# FRA_bulkhead_v1.net
KiCad netlist of a schematic drawn in EAGLE
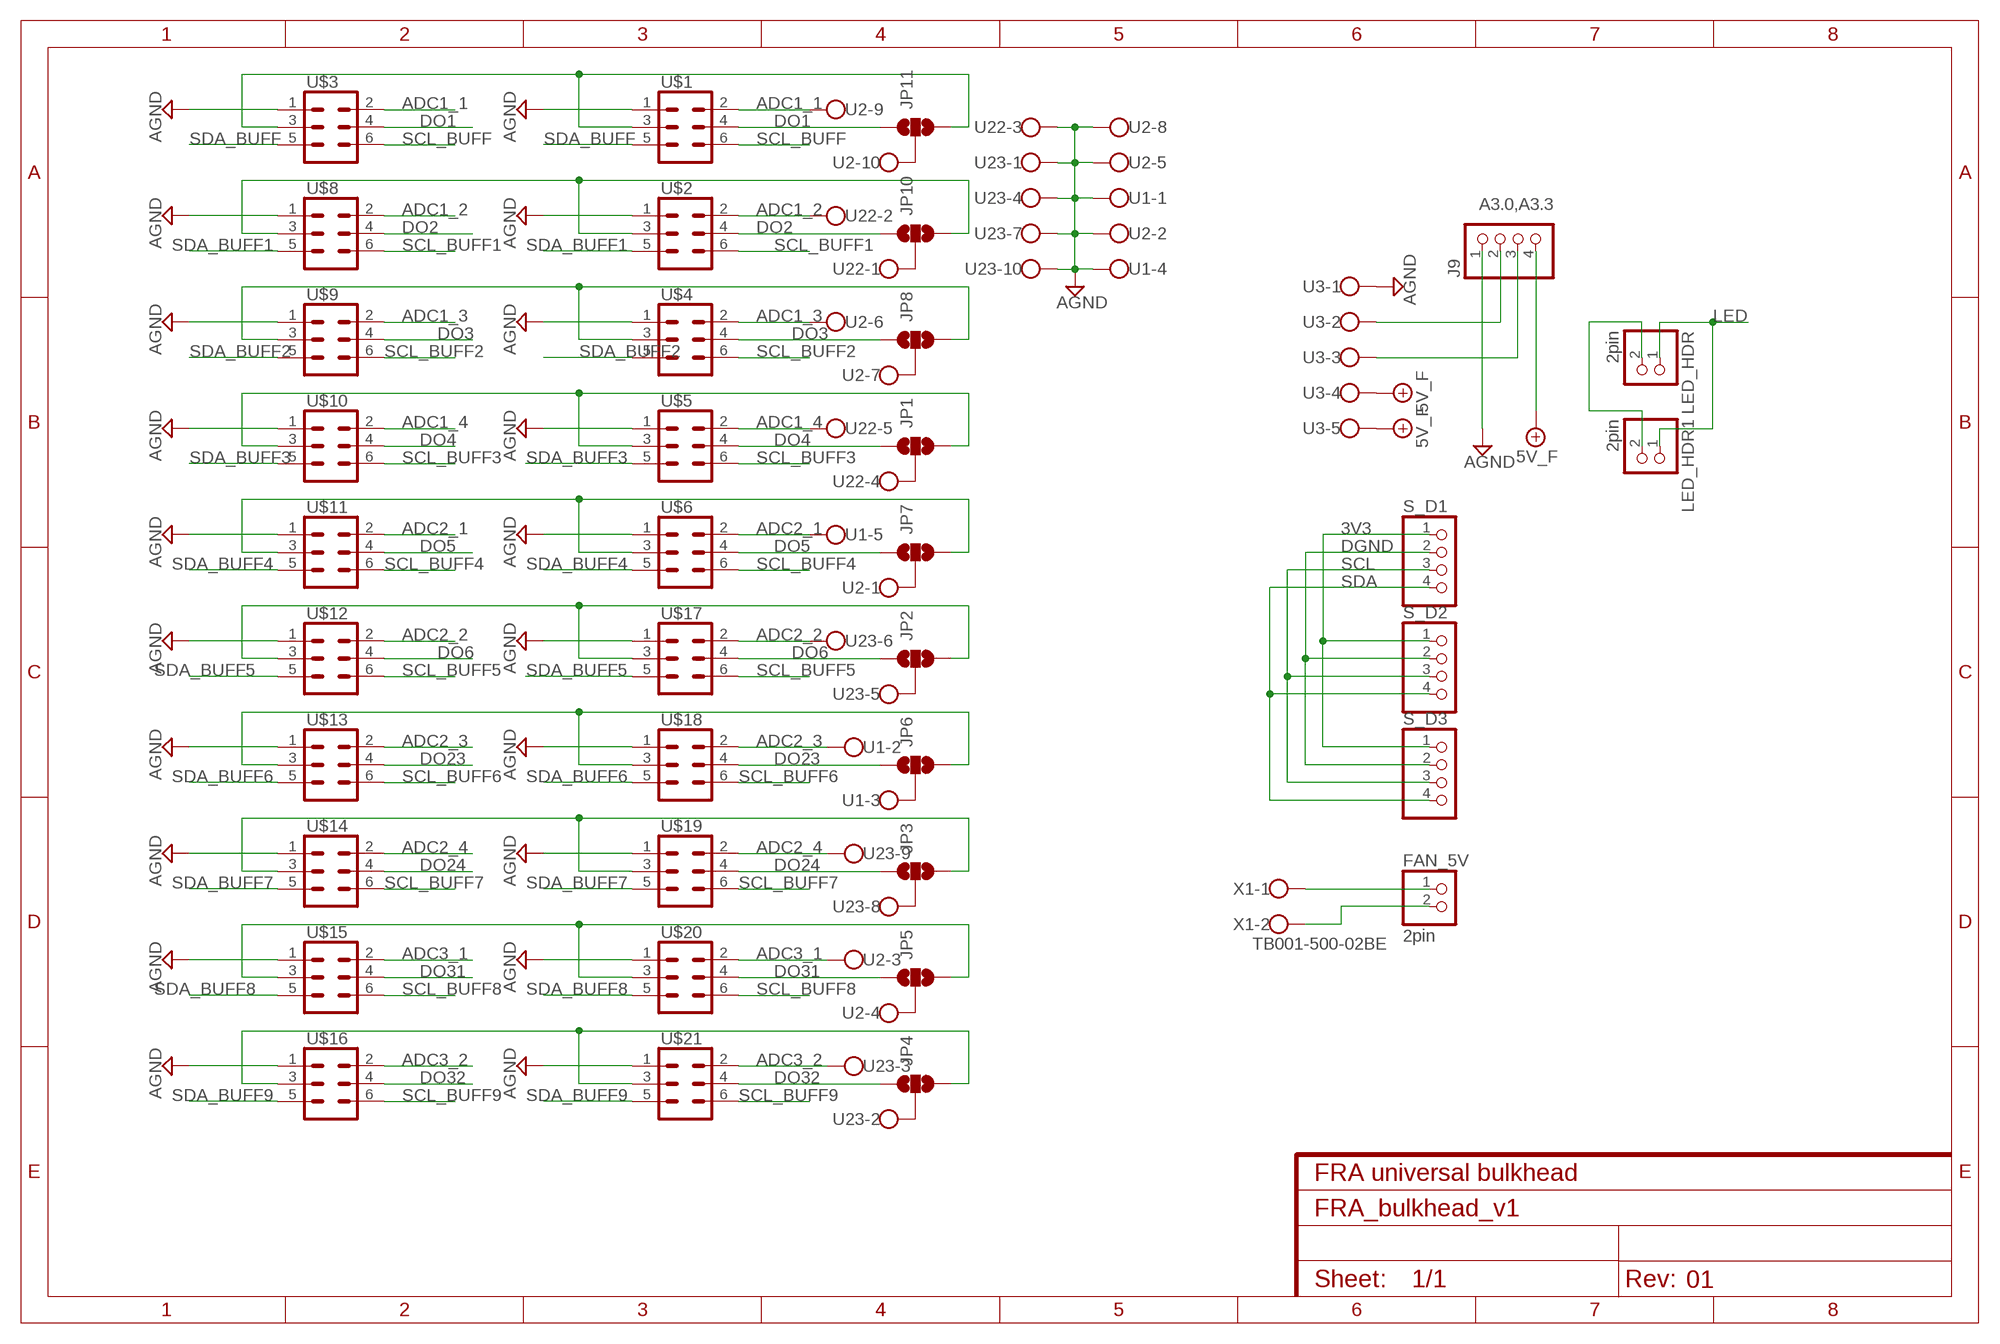
[diagram p0: schematic, sheet 1]

(export (version "E")
  (design (tool "Eeschema 10.0.6"))
  (components
    (comp (ref "FAN_5V")
      (value "2pin")
      (footprint "eagle-import:1X02")
      (fields (field (name "PARTNO") "TSW-102-07-G-S"))
      (libsource (lib "eagle-import") (part "PINHD-1X2"))
    )
    (comp (ref "J9")
      (value "4pin")
      (footprint "eagle-import:1X04")
      (fields (field (name "PARTNO") "61300411121"))
      (libsource (lib "eagle-import") (part "PINHD-1X4"))
    )
    (comp (ref "JP1")
      (value "JUMPER-SMT_3_NO_NO_SILK")
      (footprint "eagle-import:SMT-JUMPER_3_0-NO_TRACE_NO-SILK")
      (libsource (lib "eagle-import") (part "JUMPER-SMT_3_NO_NO_SILK"))
    )
    (comp (ref "JP2")
      (value "JUMPER-SMT_3_NO_NO_SILK")
      (footprint "eagle-import:SMT-JUMPER_3_0-NO_TRACE_NO-SILK")
      (libsource (lib "eagle-import") (part "JUMPER-SMT_3_NO_NO_SILK"))
    )
    (comp (ref "JP3")
      (value "JUMPER-SMT_3_NO_NO_SILK")
      (footprint "eagle-import:SMT-JUMPER_3_0-NO_TRACE_NO-SILK")
      (libsource (lib "eagle-import") (part "JUMPER-SMT_3_NO_NO_SILK"))
    )
    (comp (ref "JP4")
      (value "JUMPER-SMT_3_NO_NO_SILK")
      (footprint "eagle-import:SMT-JUMPER_3_0-NO_TRACE_NO-SILK")
      (libsource (lib "eagle-import") (part "JUMPER-SMT_3_NO_NO_SILK"))
    )
    (comp (ref "JP5")
      (value "JUMPER-SMT_3_NO_NO_SILK")
      (footprint "eagle-import:SMT-JUMPER_3_0-NO_TRACE_NO-SILK")
      (libsource (lib "eagle-import") (part "JUMPER-SMT_3_NO_NO_SILK"))
    )
    (comp (ref "JP6")
      (value "JUMPER-SMT_3_NO_NO_SILK")
      (footprint "eagle-import:SMT-JUMPER_3_0-NO_TRACE_NO-SILK")
      (libsource (lib "eagle-import") (part "JUMPER-SMT_3_NO_NO_SILK"))
    )
    (comp (ref "JP7")
      (value "JUMPER-SMT_3_NO_NO_SILK")
      (footprint "eagle-import:SMT-JUMPER_3_0-NO_TRACE_NO-SILK")
      (libsource (lib "eagle-import") (part "JUMPER-SMT_3_NO_NO_SILK"))
    )
    (comp (ref "JP8")
      (value "JUMPER-SMT_3_NO_NO_SILK")
      (footprint "eagle-import:SMT-JUMPER_3_0-NO_TRACE_NO-SILK")
      (libsource (lib "eagle-import") (part "JUMPER-SMT_3_NO_NO_SILK"))
    )
    (comp (ref "JP10")
      (value "JUMPER-SMT_3_NO_NO_SILK")
      (footprint "eagle-import:SMT-JUMPER_3_0-NO_TRACE_NO-SILK")
      (libsource (lib "eagle-import") (part "JUMPER-SMT_3_NO_NO_SILK"))
    )
    (comp (ref "JP11")
      (value "JUMPER-SMT_3_NO_NO_SILK")
      (footprint "eagle-import:SMT-JUMPER_3_0-NO_TRACE_NO-SILK")
      (libsource (lib "eagle-import") (part "JUMPER-SMT_3_NO_NO_SILK"))
    )
    (comp (ref "LED_HDR")
      (value "2pin")
      (footprint "eagle-import:1X02")
      (fields (field (name "PARTNO") "TSW-102-07-G-S"))
      (libsource (lib "eagle-import") (part "PINHD-1X2"))
    )
    (comp (ref "LED_HDR1")
      (value "2pin")
      (footprint "eagle-import:1X02")
      (fields (field (name "PARTNO") "TSW-102-07-G-S"))
      (libsource (lib "eagle-import") (part "PINHD-1X2"))
    )
    (comp (ref "S_D1")
      (value "4pin")
      (footprint "eagle-import:1X04")
      (fields (field (name "PARTNO") "61300411121"))
      (libsource (lib "eagle-import") (part "PINHD-1X4"))
    )
    (comp (ref "S_D2")
      (value "4pin")
      (footprint "eagle-import:1X04")
      (fields (field (name "PARTNO") "61300411121"))
      (libsource (lib "eagle-import") (part "PINHD-1X4"))
    )
    (comp (ref "S_D3")
      (value "4pin")
      (footprint "eagle-import:1X04")
      (fields (field (name "PARTNO") "61300411121"))
      (libsource (lib "eagle-import") (part "PINHD-1X4"))
    )
    (comp (ref "U$1")
      (value "CONN_03X2_WE_61200621621")
      (footprint "eagle-import:WE_61200621621")
      (fields (field (name "PARTNO") "61200621621"))
      (libsource (lib "eagle-import") (part "CONN_03X2_WE_61200621621"))
    )
    (comp (ref "U$2")
      (value "CONN_03X2_WE_61200621621")
      (footprint "eagle-import:WE_61200621621")
      (fields (field (name "PARTNO") "61200621621"))
      (libsource (lib "eagle-import") (part "CONN_03X2_WE_61200621621"))
    )
    (comp (ref "U$3")
      (value "CONN_03X2_WE_61200621621")
      (footprint "eagle-import:WE_61200621621")
      (fields (field (name "PARTNO") "61200621621"))
      (libsource (lib "eagle-import") (part "CONN_03X2_WE_61200621621"))
    )
    (comp (ref "U$4")
      (value "CONN_03X2_WE_61200621621")
      (footprint "eagle-import:WE_61200621621")
      (fields (field (name "PARTNO") "61200621621"))
      (libsource (lib "eagle-import") (part "CONN_03X2_WE_61200621621"))
    )
    (comp (ref "U$5")
      (value "CONN_03X2_WE_61200621621")
      (footprint "eagle-import:WE_61200621621")
      (fields (field (name "PARTNO") "61200621621"))
      (libsource (lib "eagle-import") (part "CONN_03X2_WE_61200621621"))
    )
    (comp (ref "U$6")
      (value "CONN_03X2_WE_61200621621")
      (footprint "eagle-import:WE_61200621621")
      (fields (field (name "PARTNO") "61200621621"))
      (libsource (lib "eagle-import") (part "CONN_03X2_WE_61200621621"))
    )
    (comp (ref "U$8")
      (value "CONN_03X2_WE_61200621621")
      (footprint "eagle-import:WE_61200621621")
      (fields (field (name "PARTNO") "61200621621"))
      (libsource (lib "eagle-import") (part "CONN_03X2_WE_61200621621"))
    )
    (comp (ref "U$9")
      (value "CONN_03X2_WE_61200621621")
      (footprint "eagle-import:WE_61200621621")
      (fields (field (name "PARTNO") "61200621621"))
      (libsource (lib "eagle-import") (part "CONN_03X2_WE_61200621621"))
    )
    (comp (ref "U$10")
      (value "CONN_03X2_WE_61200621621")
      (footprint "eagle-import:WE_61200621621")
      (fields (field (name "PARTNO") "61200621621"))
      (libsource (lib "eagle-import") (part "CONN_03X2_WE_61200621621"))
    )
    (comp (ref "U$11")
      (value "CONN_03X2_WE_61200621621")
      (footprint "eagle-import:WE_61200621621")
      (fields (field (name "PARTNO") "61200621621"))
      (libsource (lib "eagle-import") (part "CONN_03X2_WE_61200621621"))
    )
    (comp (ref "U$12")
      (value "CONN_03X2_WE_61200621621")
      (footprint "eagle-import:WE_61200621621")
      (fields (field (name "PARTNO") "61200621621"))
      (libsource (lib "eagle-import") (part "CONN_03X2_WE_61200621621"))
    )
    (comp (ref "U$13")
      (value "CONN_03X2_WE_61200621621")
      (footprint "eagle-import:WE_61200621621")
      (fields (field (name "PARTNO") "61200621621"))
      (libsource (lib "eagle-import") (part "CONN_03X2_WE_61200621621"))
    )
    (comp (ref "U$14")
      (value "CONN_03X2_WE_61200621621")
      (footprint "eagle-import:WE_61200621621")
      (fields (field (name "PARTNO") "61200621621"))
      (libsource (lib "eagle-import") (part "CONN_03X2_WE_61200621621"))
    )
    (comp (ref "U$15")
      (value "CONN_03X2_WE_61200621621")
      (footprint "eagle-import:WE_61200621621")
      (fields (field (name "PARTNO") "61200621621"))
      (libsource (lib "eagle-import") (part "CONN_03X2_WE_61200621621"))
    )
    (comp (ref "U$16")
      (value "CONN_03X2_WE_61200621621")
      (footprint "eagle-import:WE_61200621621")
      (fields (field (name "PARTNO") "61200621621"))
      (libsource (lib "eagle-import") (part "CONN_03X2_WE_61200621621"))
    )
    (comp (ref "U$17")
      (value "CONN_03X2_WE_61200621621")
      (footprint "eagle-import:WE_61200621621")
      (fields (field (name "PARTNO") "61200621621"))
      (libsource (lib "eagle-import") (part "CONN_03X2_WE_61200621621"))
    )
    (comp (ref "U$18")
      (value "CONN_03X2_WE_61200621621")
      (footprint "eagle-import:WE_61200621621")
      (fields (field (name "PARTNO") "61200621621"))
      (libsource (lib "eagle-import") (part "CONN_03X2_WE_61200621621"))
    )
    (comp (ref "U$19")
      (value "CONN_03X2_WE_61200621621")
      (footprint "eagle-import:WE_61200621621")
      (fields (field (name "PARTNO") "61200621621"))
      (libsource (lib "eagle-import") (part "CONN_03X2_WE_61200621621"))
    )
    (comp (ref "U$20")
      (value "CONN_03X2_WE_61200621621")
      (footprint "eagle-import:WE_61200621621")
      (fields (field (name "PARTNO") "61200621621"))
      (libsource (lib "eagle-import") (part "CONN_03X2_WE_61200621621"))
    )
    (comp (ref "U$21")
      (value "CONN_03X2_WE_61200621621")
      (footprint "eagle-import:WE_61200621621")
      (fields (field (name "PARTNO") "61200621621"))
      (libsource (lib "eagle-import") (part "CONN_03X2_WE_61200621621"))
    )
    (comp (ref "U1")
      (value "TB003V-500-P05BERIGHTANGLE-NORMAL")
      (footprint "eagle-import:TB003-500-P05BE")
      (libsource (lib "eagle-import") (part "TB003V-500-P05BERIGHTANGLE-NORMAL"))
    )
    (comp (ref "U2")
      (value "TB003V-500-P10BERIGHTANGLE-NORMAL")
      (footprint "eagle-import:TB003-500-P10BE")
      (libsource (lib "eagle-import") (part "TB003V-500-P10BERIGHTANGLE-NORMAL"))
    )
    (comp (ref "U3")
      (value "TB003V-500-P05BERIGHTANGLE-NORMAL")
      (footprint "eagle-import:TB003-500-P05BE")
      (libsource (lib "eagle-import") (part "TB003V-500-P05BERIGHTANGLE-NORMAL"))
    )
    (comp (ref "U22")
      (value "TB003V-500-P05BERIGHTANGLE-NORMAL")
      (footprint "eagle-import:TB003-500-P05BE")
      (libsource (lib "eagle-import") (part "TB003V-500-P05BERIGHTANGLE-NORMAL"))
    )
    (comp (ref "U23")
      (value "TB003V-500-P10BERIGHTANGLE-NORMAL")
      (footprint "eagle-import:TB003-500-P10BE")
      (libsource (lib "eagle-import") (part "TB003V-500-P10BERIGHTANGLE-NORMAL"))
    )
    (comp (ref "X1")
      (value "TB001-500-02BE")
      (footprint "eagle-import:W237-102")
      (fields (field (name "MPN") "237-102") (field (name "PARTNO") "TB001-500-02BE"))
      (libsource (lib "eagle-import") (part "W237-102"))
    )
  )
  (nets
    (net (code "1") (name "/3V3") (class "Default")
      (node (ref "S_D1") (pin "1") (pinfunction "1_1") (pintype "passive"))
      (node (ref "S_D2") (pin "1") (pinfunction "1_1") (pintype "passive"))
      (node (ref "S_D3") (pin "1") (pinfunction "1_1") (pintype "passive"))
    )
    (net (code "2") (name "/ADC1_1") (class "Default")
      (node (ref "U$1") (pin "2") (pinfunction "2_2") (pintype "bidirectional"))
      (node (ref "U$3") (pin "2") (pinfunction "2_2") (pintype "bidirectional"))
      (node (ref "U2") (pin "9") (pinfunction "KL_9") (pintype "passive"))
    )
    (net (code "3") (name "/ADC1_2") (class "Default")
      (node (ref "U$2") (pin "2") (pinfunction "2_2") (pintype "bidirectional"))
      (node (ref "U$8") (pin "2") (pinfunction "2_2") (pintype "bidirectional"))
      (node (ref "U22") (pin "2") (pinfunction "KL_2") (pintype "passive"))
    )
    (net (code "4") (name "/ADC1_3") (class "Default")
      (node (ref "U$4") (pin "2") (pinfunction "2_2") (pintype "bidirectional"))
      (node (ref "U$9") (pin "2") (pinfunction "2_2") (pintype "bidirectional"))
      (node (ref "U2") (pin "6") (pinfunction "KL_6") (pintype "passive"))
    )
    (net (code "5") (name "/ADC1_4") (class "Default")
      (node (ref "U$10") (pin "2") (pinfunction "2_2") (pintype "bidirectional"))
      (node (ref "U$5") (pin "2") (pinfunction "2_2") (pintype "bidirectional"))
      (node (ref "U22") (pin "5") (pinfunction "KL_5") (pintype "passive"))
    )
    (net (code "6") (name "/ADC2_1") (class "Default")
      (node (ref "U$11") (pin "2") (pinfunction "2_2") (pintype "bidirectional"))
      (node (ref "U$6") (pin "2") (pinfunction "2_2") (pintype "bidirectional"))
      (node (ref "U1") (pin "5") (pinfunction "KL_5") (pintype "passive"))
    )
    (net (code "7") (name "/ADC2_2") (class "Default")
      (node (ref "U$12") (pin "2") (pinfunction "2_2") (pintype "bidirectional"))
      (node (ref "U$17") (pin "2") (pinfunction "2_2") (pintype "bidirectional"))
      (node (ref "U23") (pin "6") (pinfunction "KL_6") (pintype "passive"))
    )
    (net (code "8") (name "/ADC2_3") (class "Default")
      (node (ref "U$13") (pin "2") (pinfunction "2_2") (pintype "bidirectional"))
      (node (ref "U$18") (pin "2") (pinfunction "2_2") (pintype "bidirectional"))
      (node (ref "U1") (pin "2") (pinfunction "KL_2") (pintype "passive"))
    )
    (net (code "9") (name "/ADC2_4") (class "Default")
      (node (ref "U$14") (pin "2") (pinfunction "2_2") (pintype "bidirectional"))
      (node (ref "U$19") (pin "2") (pinfunction "2_2") (pintype "bidirectional"))
      (node (ref "U23") (pin "9") (pinfunction "KL_9") (pintype "passive"))
    )
    (net (code "10") (name "/ADC3_1") (class "Default")
      (node (ref "U$15") (pin "2") (pinfunction "2_2") (pintype "bidirectional"))
      (node (ref "U$20") (pin "2") (pinfunction "2_2") (pintype "bidirectional"))
      (node (ref "U2") (pin "3") (pinfunction "KL_3") (pintype "passive"))
    )
    (net (code "11") (name "/ADC3_2") (class "Default")
      (node (ref "U$16") (pin "2") (pinfunction "2_2") (pintype "bidirectional"))
      (node (ref "U$21") (pin "2") (pinfunction "2_2") (pintype "bidirectional"))
      (node (ref "U23") (pin "3") (pinfunction "KL_3") (pintype "passive"))
    )
    (net (code "12") (name "/DGND") (class "Default")
      (node (ref "S_D1") (pin "2") (pinfunction "2_2") (pintype "passive"))
      (node (ref "S_D2") (pin "2") (pinfunction "2_2") (pintype "passive"))
      (node (ref "S_D3") (pin "2") (pinfunction "2_2") (pintype "passive"))
    )
    (net (code "13") (name "/DO1") (class "Default")
      (node (ref "JP11") (pin "1") (pinfunction "1_1") (pintype "passive"))
      (node (ref "U$1") (pin "4") (pinfunction "4_4") (pintype "bidirectional"))
      (node (ref "U$3") (pin "4") (pinfunction "4_4") (pintype "bidirectional"))
    )
    (net (code "14") (name "/DO2") (class "Default")
      (node (ref "JP10") (pin "1") (pinfunction "1_1") (pintype "passive"))
      (node (ref "U$2") (pin "4") (pinfunction "4_4") (pintype "bidirectional"))
      (node (ref "U$8") (pin "4") (pinfunction "4_4") (pintype "bidirectional"))
    )
    (net (code "15") (name "/DO3") (class "Default")
      (node (ref "JP8") (pin "1") (pinfunction "1_1") (pintype "passive"))
      (node (ref "U$4") (pin "4") (pinfunction "4_4") (pintype "bidirectional"))
      (node (ref "U$9") (pin "4") (pinfunction "4_4") (pintype "bidirectional"))
    )
    (net (code "16") (name "/DO4") (class "Default")
      (node (ref "JP1") (pin "1") (pinfunction "1_1") (pintype "passive"))
      (node (ref "U$10") (pin "4") (pinfunction "4_4") (pintype "bidirectional"))
      (node (ref "U$5") (pin "4") (pinfunction "4_4") (pintype "bidirectional"))
    )
    (net (code "17") (name "/DO5") (class "Default")
      (node (ref "JP7") (pin "1") (pinfunction "1_1") (pintype "passive"))
      (node (ref "U$11") (pin "4") (pinfunction "4_4") (pintype "bidirectional"))
      (node (ref "U$6") (pin "4") (pinfunction "4_4") (pintype "bidirectional"))
    )
    (net (code "18") (name "/DO6") (class "Default")
      (node (ref "JP2") (pin "1") (pinfunction "1_1") (pintype "passive"))
      (node (ref "U$12") (pin "4") (pinfunction "4_4") (pintype "bidirectional"))
      (node (ref "U$17") (pin "4") (pinfunction "4_4") (pintype "bidirectional"))
    )
    (net (code "19") (name "/DO23") (class "Default")
      (node (ref "JP6") (pin "1") (pinfunction "1_1") (pintype "passive"))
      (node (ref "U$13") (pin "4") (pinfunction "4_4") (pintype "bidirectional"))
      (node (ref "U$18") (pin "4") (pinfunction "4_4") (pintype "bidirectional"))
    )
    (net (code "20") (name "/DO24") (class "Default")
      (node (ref "JP3") (pin "1") (pinfunction "1_1") (pintype "passive"))
      (node (ref "U$14") (pin "4") (pinfunction "4_4") (pintype "bidirectional"))
      (node (ref "U$19") (pin "4") (pinfunction "4_4") (pintype "bidirectional"))
    )
    (net (code "21") (name "/DO31") (class "Default")
      (node (ref "JP5") (pin "1") (pinfunction "1_1") (pintype "passive"))
      (node (ref "U$15") (pin "4") (pinfunction "4_4") (pintype "bidirectional"))
      (node (ref "U$20") (pin "4") (pinfunction "4_4") (pintype "bidirectional"))
    )
    (net (code "22") (name "/DO32") (class "Default")
      (node (ref "JP4") (pin "1") (pinfunction "1_1") (pintype "passive"))
      (node (ref "U$16") (pin "4") (pinfunction "4_4") (pintype "bidirectional"))
      (node (ref "U$21") (pin "4") (pinfunction "4_4") (pintype "bidirectional"))
    )
    (net (code "23") (name "/LED") (class "Default")
      (node (ref "LED_HDR") (pin "1") (pinfunction "1_1") (pintype "passive"))
      (node (ref "LED_HDR1") (pin "1") (pinfunction "1_1") (pintype "passive"))
    )
    (net (code "24") (name "/SCL") (class "Default")
      (node (ref "S_D1") (pin "3") (pinfunction "3_3") (pintype "passive"))
      (node (ref "S_D2") (pin "3") (pinfunction "3_3") (pintype "passive"))
      (node (ref "S_D3") (pin "3") (pinfunction "3_3") (pintype "passive"))
    )
    (net (code "25") (name "/SCL_BUFF") (class "Default")
      (node (ref "U$1") (pin "6") (pinfunction "6_6") (pintype "bidirectional"))
      (node (ref "U$3") (pin "6") (pinfunction "6_6") (pintype "bidirectional"))
    )
    (net (code "26") (name "/SCL_BUFF1") (class "Default")
      (node (ref "U$2") (pin "6") (pinfunction "6_6") (pintype "bidirectional"))
      (node (ref "U$8") (pin "6") (pinfunction "6_6") (pintype "bidirectional"))
    )
    (net (code "27") (name "/SCL_BUFF2") (class "Default")
      (node (ref "U$4") (pin "6") (pinfunction "6_6") (pintype "bidirectional"))
      (node (ref "U$9") (pin "6") (pinfunction "6_6") (pintype "bidirectional"))
    )
    (net (code "28") (name "/SCL_BUFF3") (class "Default")
      (node (ref "U$10") (pin "6") (pinfunction "6_6") (pintype "bidirectional"))
      (node (ref "U$5") (pin "6") (pinfunction "6_6") (pintype "bidirectional"))
    )
    (net (code "29") (name "/SCL_BUFF4") (class "Default")
      (node (ref "U$11") (pin "6") (pinfunction "6_6") (pintype "bidirectional"))
      (node (ref "U$6") (pin "6") (pinfunction "6_6") (pintype "bidirectional"))
    )
    (net (code "30") (name "/SCL_BUFF5") (class "Default")
      (node (ref "U$12") (pin "6") (pinfunction "6_6") (pintype "bidirectional"))
      (node (ref "U$17") (pin "6") (pinfunction "6_6") (pintype "bidirectional"))
    )
    (net (code "31") (name "/SCL_BUFF6") (class "Default")
      (node (ref "U$13") (pin "6") (pinfunction "6_6") (pintype "bidirectional"))
      (node (ref "U$18") (pin "6") (pinfunction "6_6") (pintype "bidirectional"))
    )
    (net (code "32") (name "/SCL_BUFF7") (class "Default")
      (node (ref "U$14") (pin "6") (pinfunction "6_6") (pintype "bidirectional"))
      (node (ref "U$19") (pin "6") (pinfunction "6_6") (pintype "bidirectional"))
    )
    (net (code "33") (name "/SCL_BUFF8") (class "Default")
      (node (ref "U$15") (pin "6") (pinfunction "6_6") (pintype "bidirectional"))
      (node (ref "U$20") (pin "6") (pinfunction "6_6") (pintype "bidirectional"))
    )
    (net (code "34") (name "/SCL_BUFF9") (class "Default")
      (node (ref "U$16") (pin "6") (pinfunction "6_6") (pintype "bidirectional"))
      (node (ref "U$21") (pin "6") (pinfunction "6_6") (pintype "bidirectional"))
    )
    (net (code "35") (name "/SDA") (class "Default")
      (node (ref "S_D1") (pin "4") (pinfunction "4_4") (pintype "passive"))
      (node (ref "S_D2") (pin "4") (pinfunction "4_4") (pintype "passive"))
      (node (ref "S_D3") (pin "4") (pinfunction "4_4") (pintype "passive"))
    )
    (net (code "36") (name "/SDA_BUFF") (class "Default")
      (node (ref "U$1") (pin "5") (pinfunction "5_5") (pintype "bidirectional"))
      (node (ref "U$3") (pin "5") (pinfunction "5_5") (pintype "bidirectional"))
    )
    (net (code "37") (name "/SDA_BUFF1") (class "Default")
      (node (ref "U$2") (pin "5") (pinfunction "5_5") (pintype "bidirectional"))
      (node (ref "U$8") (pin "5") (pinfunction "5_5") (pintype "bidirectional"))
    )
    (net (code "38") (name "/SDA_BUFF2") (class "Default")
      (node (ref "U$4") (pin "5") (pinfunction "5_5") (pintype "bidirectional"))
      (node (ref "U$9") (pin "5") (pinfunction "5_5") (pintype "bidirectional"))
    )
    (net (code "39") (name "/SDA_BUFF3") (class "Default")
      (node (ref "U$10") (pin "5") (pinfunction "5_5") (pintype "bidirectional"))
      (node (ref "U$5") (pin "5") (pinfunction "5_5") (pintype "bidirectional"))
    )
    (net (code "40") (name "/SDA_BUFF4") (class "Default")
      (node (ref "U$11") (pin "5") (pinfunction "5_5") (pintype "bidirectional"))
      (node (ref "U$6") (pin "5") (pinfunction "5_5") (pintype "bidirectional"))
    )
    (net (code "41") (name "/SDA_BUFF5") (class "Default")
      (node (ref "U$12") (pin "5") (pinfunction "5_5") (pintype "bidirectional"))
      (node (ref "U$17") (pin "5") (pinfunction "5_5") (pintype "bidirectional"))
    )
    (net (code "42") (name "/SDA_BUFF6") (class "Default")
      (node (ref "U$13") (pin "5") (pinfunction "5_5") (pintype "bidirectional"))
      (node (ref "U$18") (pin "5") (pinfunction "5_5") (pintype "bidirectional"))
    )
    (net (code "43") (name "/SDA_BUFF7") (class "Default")
      (node (ref "U$14") (pin "5") (pinfunction "5_5") (pintype "bidirectional"))
      (node (ref "U$19") (pin "5") (pinfunction "5_5") (pintype "bidirectional"))
    )
    (net (code "44") (name "/SDA_BUFF8") (class "Default")
      (node (ref "U$15") (pin "5") (pinfunction "5_5") (pintype "bidirectional"))
      (node (ref "U$20") (pin "5") (pinfunction "5_5") (pintype "bidirectional"))
    )
    (net (code "45") (name "/SDA_BUFF9") (class "Default")
      (node (ref "U$16") (pin "5") (pinfunction "5_5") (pintype "bidirectional"))
      (node (ref "U$21") (pin "5") (pinfunction "5_5") (pintype "bidirectional"))
    )
    (net (code "46") (name "5V_F") (class "Default")
      (node (ref "J9") (pin "4") (pinfunction "4_4") (pintype "passive"))
      (node (ref "U3") (pin "4") (pinfunction "KL_4") (pintype "passive"))
      (node (ref "U3") (pin "5") (pinfunction "KL_5") (pintype "passive"))
    )
    (net (code "47") (name "AGND") (class "Default")
      (node (ref "J9") (pin "1") (pinfunction "1_1") (pintype "passive"))
      (node (ref "U$1") (pin "1") (pinfunction "1_1") (pintype "bidirectional"))
      (node (ref "U$10") (pin "1") (pinfunction "1_1") (pintype "bidirectional"))
      (node (ref "U$11") (pin "1") (pinfunction "1_1") (pintype "bidirectional"))
      (node (ref "U$12") (pin "1") (pinfunction "1_1") (pintype "bidirectional"))
      (node (ref "U$13") (pin "1") (pinfunction "1_1") (pintype "bidirectional"))
      (node (ref "U$14") (pin "1") (pinfunction "1_1") (pintype "bidirectional"))
      (node (ref "U$15") (pin "1") (pinfunction "1_1") (pintype "bidirectional"))
      (node (ref "U$16") (pin "1") (pinfunction "1_1") (pintype "bidirectional"))
      (node (ref "U$17") (pin "1") (pinfunction "1_1") (pintype "bidirectional"))
      (node (ref "U$18") (pin "1") (pinfunction "1_1") (pintype "bidirectional"))
      (node (ref "U$19") (pin "1") (pinfunction "1_1") (pintype "bidirectional"))
      (node (ref "U$2") (pin "1") (pinfunction "1_1") (pintype "bidirectional"))
      (node (ref "U$20") (pin "1") (pinfunction "1_1") (pintype "bidirectional"))
      (node (ref "U$21") (pin "1") (pinfunction "1_1") (pintype "bidirectional"))
      (node (ref "U$3") (pin "1") (pinfunction "1_1") (pintype "bidirectional"))
      (node (ref "U$4") (pin "1") (pinfunction "1_1") (pintype "bidirectional"))
      (node (ref "U$5") (pin "1") (pinfunction "1_1") (pintype "bidirectional"))
      (node (ref "U$6") (pin "1") (pinfunction "1_1") (pintype "bidirectional"))
      (node (ref "U$8") (pin "1") (pinfunction "1_1") (pintype "bidirectional"))
      (node (ref "U$9") (pin "1") (pinfunction "1_1") (pintype "bidirectional"))
      (node (ref "U1") (pin "1") (pinfunction "KL_1") (pintype "passive"))
      (node (ref "U1") (pin "4") (pinfunction "KL_4") (pintype "passive"))
      (node (ref "U2") (pin "2") (pinfunction "KL_2") (pintype "passive"))
      (node (ref "U2") (pin "5") (pinfunction "KL_5") (pintype "passive"))
      (node (ref "U2") (pin "8") (pinfunction "KL_8") (pintype "passive"))
      (node (ref "U22") (pin "3") (pinfunction "KL_3") (pintype "passive"))
      (node (ref "U23") (pin "1") (pinfunction "KL_1") (pintype "passive"))
      (node (ref "U23") (pin "10") (pinfunction "KL_10") (pintype "passive"))
      (node (ref "U23") (pin "4") (pinfunction "KL_4") (pintype "passive"))
      (node (ref "U23") (pin "7") (pinfunction "KL_7") (pintype "passive"))
      (node (ref "U3") (pin "1") (pinfunction "KL_1") (pintype "passive"))
    )
    (net (code "48") (name "Net-(JP1-Pad3)") (class "Default")
      (node (ref "JP1") (pin "3") (pinfunction "3_3") (pintype "passive"))
      (node (ref "U$10") (pin "3") (pinfunction "3_3") (pintype "bidirectional"))
      (node (ref "U$5") (pin "3") (pinfunction "3_3") (pintype "bidirectional"))
    )
    (net (code "49") (name "Net-(JP2-Pad3)") (class "Default")
      (node (ref "JP2") (pin "3") (pinfunction "3_3") (pintype "passive"))
      (node (ref "U$12") (pin "3") (pinfunction "3_3") (pintype "bidirectional"))
      (node (ref "U$17") (pin "3") (pinfunction "3_3") (pintype "bidirectional"))
    )
    (net (code "50") (name "Net-(JP3-Pad3)") (class "Default")
      (node (ref "JP3") (pin "3") (pinfunction "3_3") (pintype "passive"))
      (node (ref "U$14") (pin "3") (pinfunction "3_3") (pintype "bidirectional"))
      (node (ref "U$19") (pin "3") (pinfunction "3_3") (pintype "bidirectional"))
    )
    (net (code "51") (name "Net-(JP4-Pad3)") (class "Default")
      (node (ref "JP4") (pin "3") (pinfunction "3_3") (pintype "passive"))
      (node (ref "U$16") (pin "3") (pinfunction "3_3") (pintype "bidirectional"))
      (node (ref "U$21") (pin "3") (pinfunction "3_3") (pintype "bidirectional"))
    )
    (net (code "52") (name "Net-(JP5-Pad3)") (class "Default")
      (node (ref "JP5") (pin "3") (pinfunction "3_3") (pintype "passive"))
      (node (ref "U$15") (pin "3") (pinfunction "3_3") (pintype "bidirectional"))
      (node (ref "U$20") (pin "3") (pinfunction "3_3") (pintype "bidirectional"))
    )
    (net (code "53") (name "Net-(JP6-Pad3)") (class "Default")
      (node (ref "JP6") (pin "3") (pinfunction "3_3") (pintype "passive"))
      (node (ref "U$13") (pin "3") (pinfunction "3_3") (pintype "bidirectional"))
      (node (ref "U$18") (pin "3") (pinfunction "3_3") (pintype "bidirectional"))
    )
    (net (code "54") (name "Net-(JP7-Pad3)") (class "Default")
      (node (ref "JP7") (pin "3") (pinfunction "3_3") (pintype "passive"))
      (node (ref "U$11") (pin "3") (pinfunction "3_3") (pintype "bidirectional"))
      (node (ref "U$6") (pin "3") (pinfunction "3_3") (pintype "bidirectional"))
    )
    (net (code "55") (name "Net-(JP8-Pad3)") (class "Default")
      (node (ref "JP8") (pin "3") (pinfunction "3_3") (pintype "passive"))
      (node (ref "U$4") (pin "3") (pinfunction "3_3") (pintype "bidirectional"))
      (node (ref "U$9") (pin "3") (pinfunction "3_3") (pintype "bidirectional"))
    )
    (net (code "56") (name "Net-(JP10-Pad3)") (class "Default")
      (node (ref "JP10") (pin "3") (pinfunction "3_3") (pintype "passive"))
      (node (ref "U$2") (pin "3") (pinfunction "3_3") (pintype "bidirectional"))
      (node (ref "U$8") (pin "3") (pinfunction "3_3") (pintype "bidirectional"))
    )
    (net (code "57") (name "Net-(JP11-Pad3)") (class "Default")
      (node (ref "JP11") (pin "3") (pinfunction "3_3") (pintype "passive"))
      (node (ref "U$1") (pin "3") (pinfunction "3_3") (pintype "bidirectional"))
      (node (ref "U$3") (pin "3") (pinfunction "3_3") (pintype "bidirectional"))
    )
    (net (code "58") (name "Net-(LED_HDR-Pad2)") (class "Default")
      (node (ref "LED_HDR") (pin "2") (pinfunction "2_2") (pintype "passive"))
      (node (ref "LED_HDR1") (pin "2") (pinfunction "2_2") (pintype "passive"))
    )
    (net (code "59") (name "Net-(U1C-KL)") (class "Default")
      (node (ref "JP6") (pin "2") (pinfunction "2_2") (pintype "passive"))
      (node (ref "U1") (pin "3") (pinfunction "KL_3") (pintype "passive"))
    )
    (net (code "60") (name "Net-(U2A-KL)") (class "Default")
      (node (ref "JP7") (pin "2") (pinfunction "2_2") (pintype "passive"))
      (node (ref "U2") (pin "1") (pinfunction "KL_1") (pintype "passive"))
    )
    (net (code "61") (name "Net-(U2B-KL)") (class "Default")
      (node (ref "JP11") (pin "2") (pinfunction "2_2") (pintype "passive"))
      (node (ref "U2") (pin "10") (pinfunction "KL_10") (pintype "passive"))
    )
    (net (code "62") (name "Net-(U2E-KL)") (class "Default")
      (node (ref "JP5") (pin "2") (pinfunction "2_2") (pintype "passive"))
      (node (ref "U2") (pin "4") (pinfunction "KL_4") (pintype "passive"))
    )
    (net (code "63") (name "Net-(U2H-KL)") (class "Default")
      (node (ref "JP8") (pin "2") (pinfunction "2_2") (pintype "passive"))
      (node (ref "U2") (pin "7") (pinfunction "KL_7") (pintype "passive"))
    )
    (net (code "64") (name "Net-(U3B-KL)") (class "Default")
      (node (ref "J9") (pin "2") (pinfunction "2_2") (pintype "passive"))
      (node (ref "U3") (pin "2") (pinfunction "KL_2") (pintype "passive"))
    )
    (net (code "65") (name "Net-(U3C-KL)") (class "Default")
      (node (ref "J9") (pin "3") (pinfunction "3_3") (pintype "passive"))
      (node (ref "U3") (pin "3") (pinfunction "KL_3") (pintype "passive"))
    )
    (net (code "66") (name "Net-(U22A-KL)") (class "Default")
      (node (ref "JP10") (pin "2") (pinfunction "2_2") (pintype "passive"))
      (node (ref "U22") (pin "1") (pinfunction "KL_1") (pintype "passive"))
    )
    (net (code "67") (name "Net-(U22D-KL)") (class "Default")
      (node (ref "JP1") (pin "2") (pinfunction "2_2") (pintype "passive"))
      (node (ref "U22") (pin "4") (pinfunction "KL_4") (pintype "passive"))
    )
    (net (code "68") (name "Net-(U23C-KL)") (class "Default")
      (node (ref "JP4") (pin "2") (pinfunction "2_2") (pintype "passive"))
      (node (ref "U23") (pin "2") (pinfunction "KL_2") (pintype "passive"))
    )
    (net (code "69") (name "Net-(U23F-KL)") (class "Default")
      (node (ref "JP2") (pin "2") (pinfunction "2_2") (pintype "passive"))
      (node (ref "U23") (pin "5") (pinfunction "KL_5") (pintype "passive"))
    )
    (net (code "70") (name "Net-(U23I-KL)") (class "Default")
      (node (ref "JP3") (pin "2") (pinfunction "2_2") (pintype "passive"))
      (node (ref "U23") (pin "8") (pinfunction "KL_8") (pintype "passive"))
    )
    (net (code "71") (name "Net-(X1A-KL)") (class "Default")
      (node (ref "FAN_5V") (pin "1") (pinfunction "1_1") (pintype "passive"))
      (node (ref "X1") (pin "1") (pinfunction "KL_1") (pintype "passive"))
    )
    (net (code "72") (name "Net-(X1B-KL)") (class "Default")
      (node (ref "FAN_5V") (pin "2") (pinfunction "2_2") (pintype "passive"))
      (node (ref "X1") (pin "2") (pinfunction "KL_2") (pintype "passive"))
    )
  )
)
